# Charging.net
KiCad netlist of a schematic drawn in Altium Designer
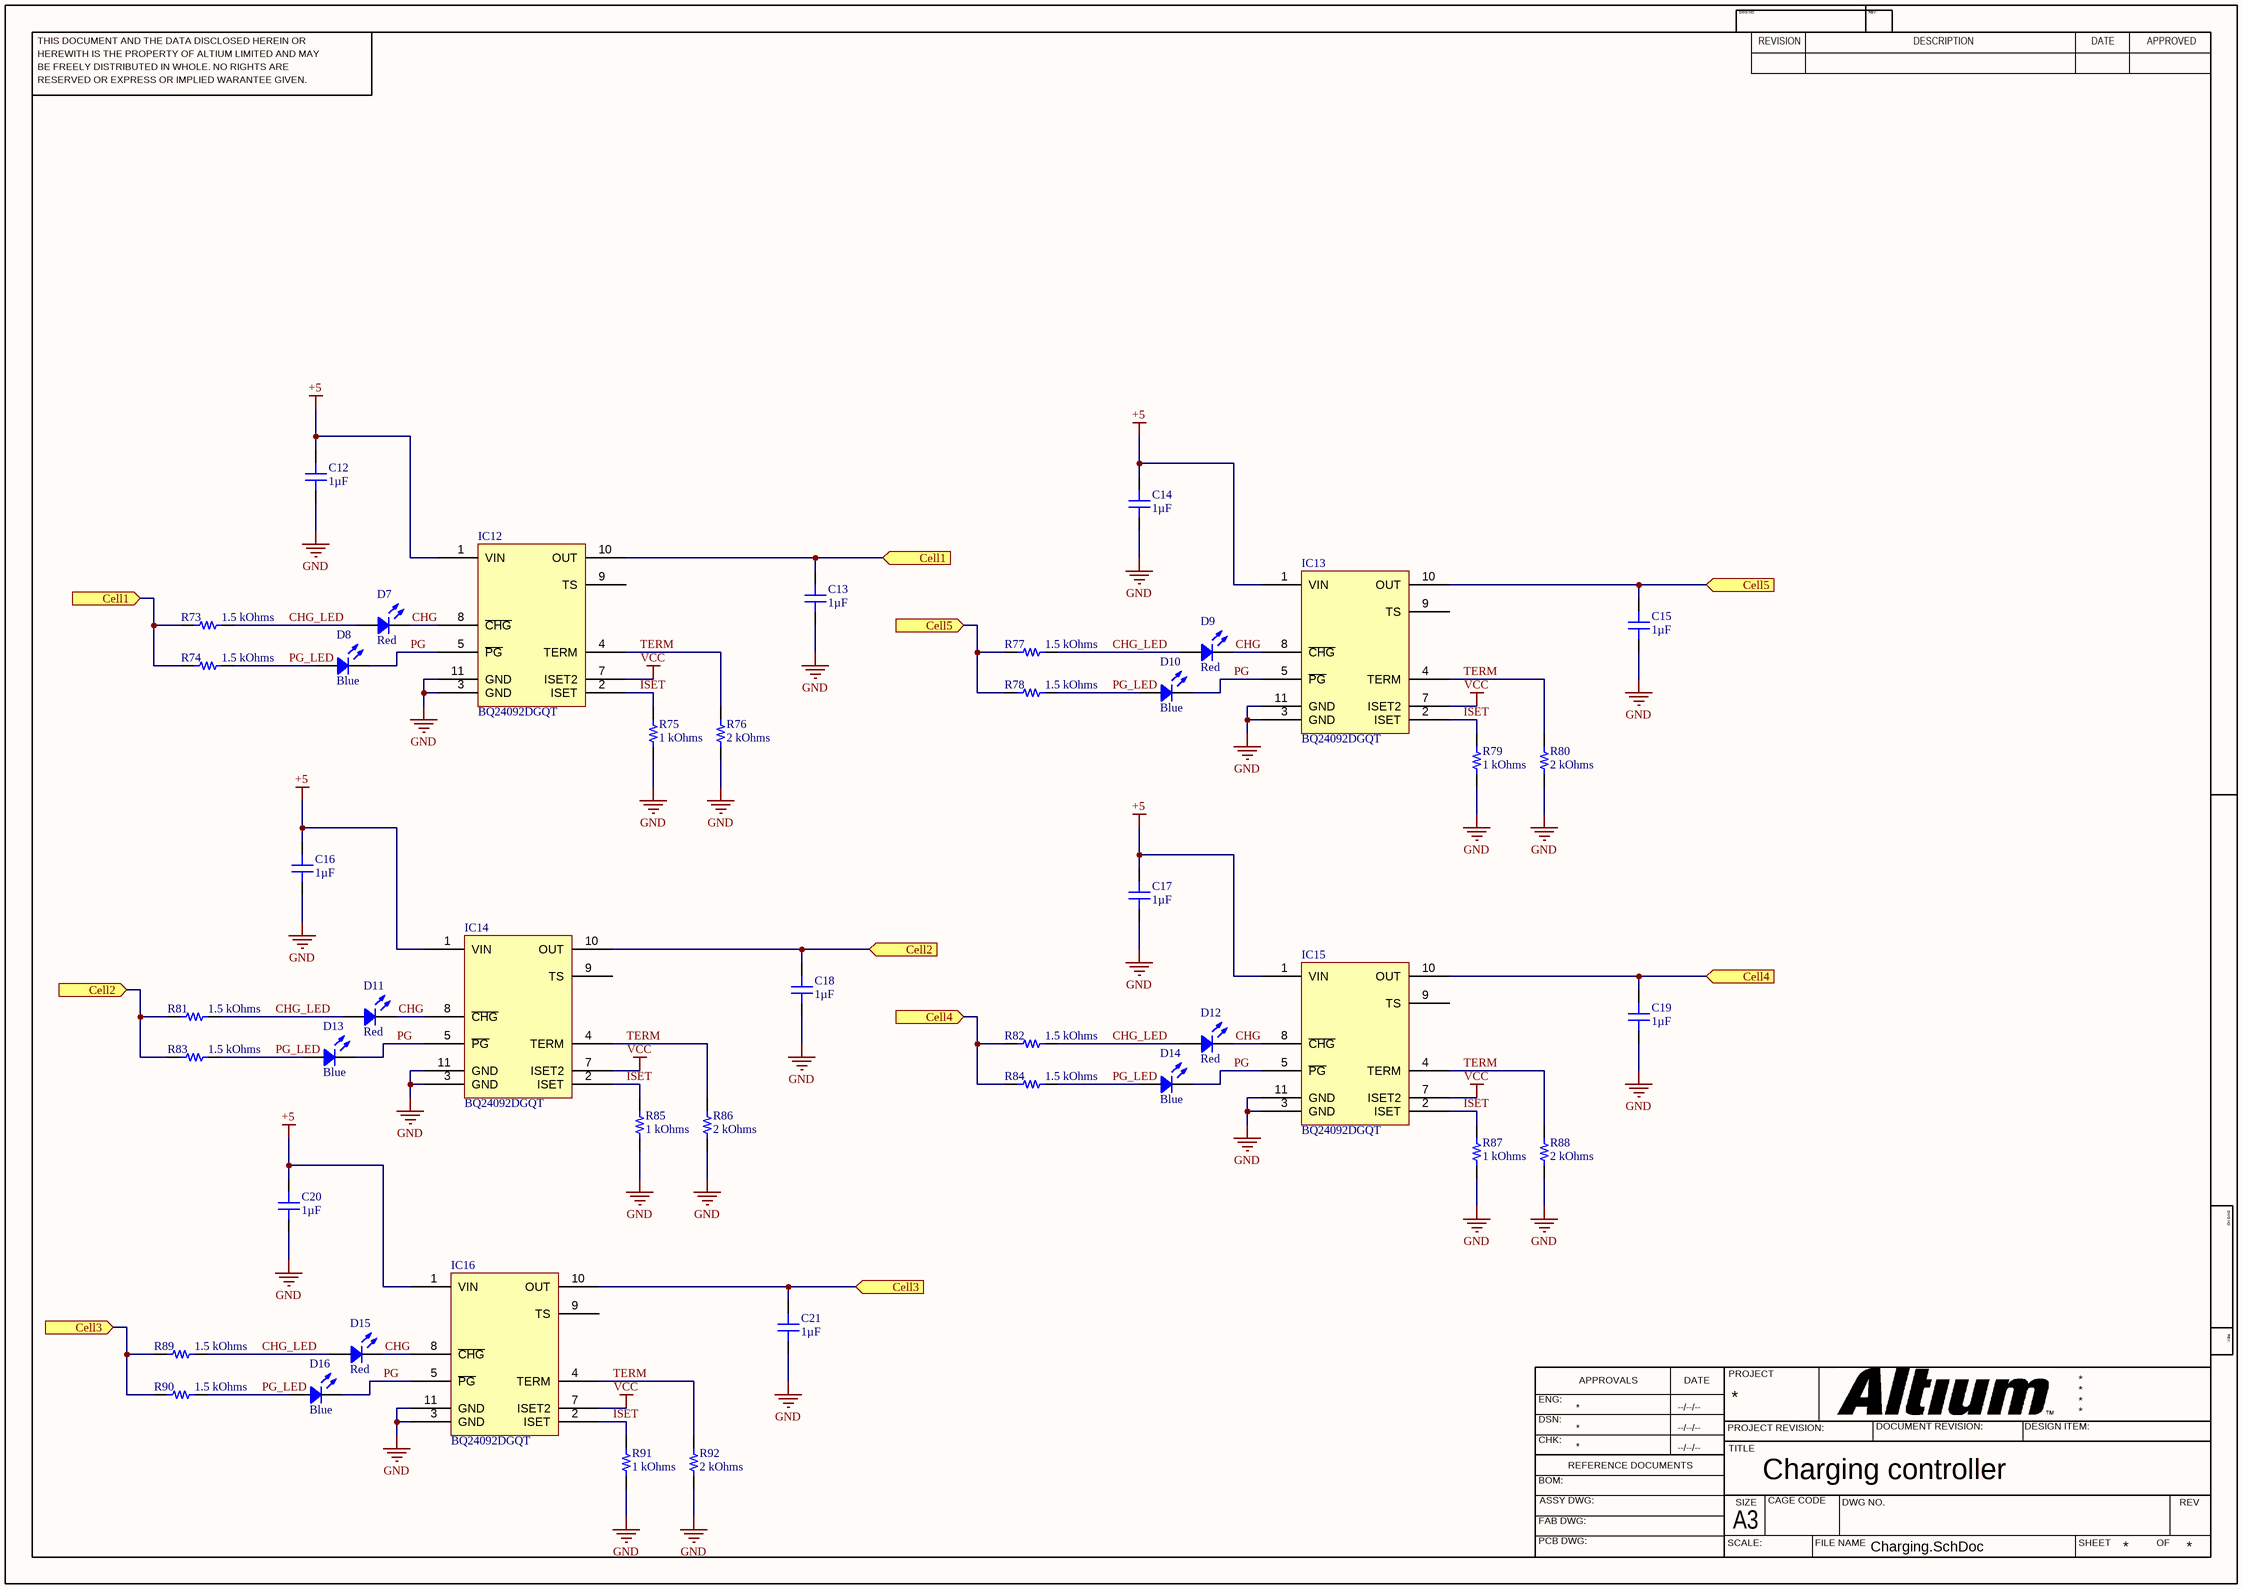
[diagram p0: Charging.SchDoc]

(export (version "E")
  (design (tool "Eeschema 10.0.6"))
  (components
    (comp (ref "C12")
      (value "1µF")
      (footprint "CAP 0603_1608")
      (description "CAP CER 1UF 25V X5R 0603")
      (fields (field (name "PART NUMBER") "CC0603KRX5R8BB105") (field (name "MANUFACTURER") "Yageo"))
      (libsource (lib "Celestial Altium Library - altium_library") (part "Capacitor"))
    )
    (comp (ref "C13")
      (value "1µF")
      (footprint "CAP 0603_1608")
      (description "CAP CER 1UF 25V X5R 0603")
      (fields (field (name "PART NUMBER") "CC0603KRX5R8BB105") (field (name "MANUFACTURER") "Yageo"))
      (libsource (lib "Celestial Altium Library - altium_library") (part "Capacitor"))
    )
    (comp (ref "C14")
      (value "1µF")
      (footprint "CAP 0603_1608")
      (description "CAP CER 1UF 25V X5R 0603")
      (fields (field (name "PART NUMBER") "CC0603KRX5R8BB105") (field (name "MANUFACTURER") "Yageo"))
      (libsource (lib "Celestial Altium Library - altium_library") (part "Capacitor"))
    )
    (comp (ref "C15")
      (value "1µF")
      (footprint "CAP 0603_1608")
      (description "CAP CER 1UF 25V X5R 0603")
      (fields (field (name "PART NUMBER") "CC0603KRX5R8BB105") (field (name "MANUFACTURER") "Yageo"))
      (libsource (lib "Celestial Altium Library - altium_library") (part "Capacitor"))
    )
    (comp (ref "C16")
      (value "1µF")
      (footprint "CAP 0603_1608")
      (description "CAP CER 1UF 25V X5R 0603")
      (fields (field (name "PART NUMBER") "CC0603KRX5R8BB105") (field (name "MANUFACTURER") "Yageo"))
      (libsource (lib "Celestial Altium Library - altium_library") (part "Capacitor"))
    )
    (comp (ref "C17")
      (value "1µF")
      (footprint "CAP 0603_1608")
      (description "CAP CER 1UF 25V X5R 0603")
      (fields (field (name "PART NUMBER") "CC0603KRX5R8BB105") (field (name "MANUFACTURER") "Yageo"))
      (libsource (lib "Celestial Altium Library - altium_library") (part "Capacitor"))
    )
    (comp (ref "C18")
      (value "1µF")
      (footprint "CAP 0603_1608")
      (description "CAP CER 1UF 25V X5R 0603")
      (fields (field (name "PART NUMBER") "CC0603KRX5R8BB105") (field (name "MANUFACTURER") "Yageo"))
      (libsource (lib "Celestial Altium Library - altium_library") (part "Capacitor"))
    )
    (comp (ref "C19")
      (value "1µF")
      (footprint "CAP 0603_1608")
      (description "CAP CER 1UF 25V X5R 0603")
      (fields (field (name "PART NUMBER") "CC0603KRX5R8BB105") (field (name "MANUFACTURER") "Yageo"))
      (libsource (lib "Celestial Altium Library - altium_library") (part "Capacitor"))
    )
    (comp (ref "C20")
      (value "1µF")
      (footprint "CAP 0603_1608")
      (description "CAP CER 1UF 25V X5R 0603")
      (fields (field (name "PART NUMBER") "CC0603KRX5R8BB105") (field (name "MANUFACTURER") "Yageo"))
      (libsource (lib "Celestial Altium Library - altium_library") (part "Capacitor"))
    )
    (comp (ref "C21")
      (value "1µF")
      (footprint "CAP 0603_1608")
      (description "CAP CER 1UF 25V X5R 0603")
      (fields (field (name "PART NUMBER") "CC0603KRX5R8BB105") (field (name "MANUFACTURER") "Yageo"))
      (libsource (lib "Celestial Altium Library - altium_library") (part "Capacitor"))
    )
    (comp (ref "D7")
      (value "Red")
      (footprint "LED 0603_1608 RED")
      (description "LED RED CLEAR 2SMD")
      (fields
        (field (name "PART NUMBER") "19-213USRC/S259/TR8")
        (field (name "MANUFACTURER") "Everlight Electronics Co Ltd")
      )
      (libsource (lib "Celestial Altium Library - altium_library") (part "LED"))
    )
    (comp (ref "D8")
      (value "Blue")
      (footprint "LED 0603_1608 BLUE")
      (description "LED BLUE CLEAR 2SMD")
      (fields
        (field (name "PART NUMBER") "EAST16084BA8")
        (field (name "MANUFACTURER") "Everlight Electronics Co Ltd")
      )
      (libsource (lib "Celestial Altium Library - altium_library") (part "LED"))
    )
    (comp (ref "D9")
      (value "Red")
      (footprint "LED 0603_1608 RED")
      (description "LED RED CLEAR 2SMD")
      (fields
        (field (name "PART NUMBER") "19-213USRC/S259/TR8")
        (field (name "MANUFACTURER") "Everlight Electronics Co Ltd")
      )
      (libsource (lib "Celestial Altium Library - altium_library") (part "LED"))
    )
    (comp (ref "D10")
      (value "Blue")
      (footprint "LED 0603_1608 BLUE")
      (description "LED BLUE CLEAR 2SMD")
      (fields
        (field (name "PART NUMBER") "EAST16084BA8")
        (field (name "MANUFACTURER") "Everlight Electronics Co Ltd")
      )
      (libsource (lib "Celestial Altium Library - altium_library") (part "LED"))
    )
    (comp (ref "D11")
      (value "Red")
      (footprint "LED 0603_1608 RED")
      (description "LED RED CLEAR 2SMD")
      (fields
        (field (name "PART NUMBER") "19-213USRC/S259/TR8")
        (field (name "MANUFACTURER") "Everlight Electronics Co Ltd")
      )
      (libsource (lib "Celestial Altium Library - altium_library") (part "LED"))
    )
    (comp (ref "D12")
      (value "Red")
      (footprint "LED 0603_1608 RED")
      (description "LED RED CLEAR 2SMD")
      (fields
        (field (name "PART NUMBER") "19-213USRC/S259/TR8")
        (field (name "MANUFACTURER") "Everlight Electronics Co Ltd")
      )
      (libsource (lib "Celestial Altium Library - altium_library") (part "LED"))
    )
    (comp (ref "D13")
      (value "Blue")
      (footprint "LED 0603_1608 BLUE")
      (description "LED BLUE CLEAR 2SMD")
      (fields
        (field (name "PART NUMBER") "EAST16084BA8")
        (field (name "MANUFACTURER") "Everlight Electronics Co Ltd")
      )
      (libsource (lib "Celestial Altium Library - altium_library") (part "LED"))
    )
    (comp (ref "D14")
      (value "Blue")
      (footprint "LED 0603_1608 BLUE")
      (description "LED BLUE CLEAR 2SMD")
      (fields
        (field (name "PART NUMBER") "EAST16084BA8")
        (field (name "MANUFACTURER") "Everlight Electronics Co Ltd")
      )
      (libsource (lib "Celestial Altium Library - altium_library") (part "LED"))
    )
    (comp (ref "D15")
      (value "Red")
      (footprint "LED 0603_1608 RED")
      (description "LED RED CLEAR 2SMD")
      (fields
        (field (name "PART NUMBER") "19-213USRC/S259/TR8")
        (field (name "MANUFACTURER") "Everlight Electronics Co Ltd")
      )
      (libsource (lib "Celestial Altium Library - altium_library") (part "LED"))
    )
    (comp (ref "D16")
      (value "Blue")
      (footprint "LED 0603_1608 BLUE")
      (description "LED BLUE CLEAR 2SMD")
      (fields
        (field (name "PART NUMBER") "EAST16084BA8")
        (field (name "MANUFACTURER") "Everlight Electronics Co Ltd")
      )
      (libsource (lib "Celestial Altium Library - altium_library") (part "LED"))
    )
    (comp (ref "IC12")
      (value "BQ24092DGQT")
      (footprint "TI PDSO-10 DCQ")
      (description "IC BATT CHARGER LI-ION 10MSOP")
      (fields (field (name "MANUFACTURER") "Texas Instruments"))
      (libsource (lib "Celestial Altium Library - altium_library") (part "TI BQ2409x"))
    )
    (comp (ref "IC13")
      (value "BQ24092DGQT")
      (footprint "TI PDSO-10 DCQ")
      (description "IC BATT CHARGER LI-ION 10MSOP")
      (fields (field (name "MANUFACTURER") "Texas Instruments"))
      (libsource (lib "Celestial Altium Library - altium_library") (part "TI BQ2409x"))
    )
    (comp (ref "IC14")
      (value "BQ24092DGQT")
      (footprint "TI PDSO-10 DCQ")
      (description "IC BATT CHARGER LI-ION 10MSOP")
      (fields (field (name "MANUFACTURER") "Texas Instruments"))
      (libsource (lib "Celestial Altium Library - altium_library") (part "TI BQ2409x"))
    )
    (comp (ref "IC15")
      (value "BQ24092DGQT")
      (footprint "TI PDSO-10 DCQ")
      (description "IC BATT CHARGER LI-ION 10MSOP")
      (fields (field (name "MANUFACTURER") "Texas Instruments"))
      (libsource (lib "Celestial Altium Library - altium_library") (part "TI BQ2409x"))
    )
    (comp (ref "IC16")
      (value "BQ24092DGQT")
      (footprint "TI PDSO-10 DCQ")
      (description "IC BATT CHARGER LI-ION 10MSOP")
      (fields (field (name "MANUFACTURER") "Texas Instruments"))
      (libsource (lib "Celestial Altium Library - altium_library") (part "TI BQ2409x"))
    )
    (comp (ref "R73")
      (value "1.5 kOhms")
      (footprint "RES 0603_1608")
      (description "RES SMD 1.5K OHM 1% 1/10W 0603")
      (fields
        (field (name "PART NUMBER") "ERJ-3EKF1501V")
        (field (name "MANUFACTURER") "Panasonic Electronic Components")
      )
      (libsource (lib "Celestial Altium Library - altium_library") (part "Resistor"))
    )
    (comp (ref "R74")
      (value "1.5 kOhms")
      (footprint "RES 0603_1608")
      (description "RES SMD 1.5K OHM 1% 1/10W 0603")
      (fields
        (field (name "PART NUMBER") "ERJ-3EKF1501V")
        (field (name "MANUFACTURER") "Panasonic Electronic Components")
      )
      (libsource (lib "Celestial Altium Library - altium_library") (part "Resistor"))
    )
    (comp (ref "R75")
      (value "1 kOhms")
      (footprint "RES 0603_1608")
      (description "RES SMD 1K OHM 5% 1/4W 0603")
      (fields
        (field (name "PART NUMBER") "ERJ-PA3J102V")
        (field (name "MANUFACTURER") "Panasonic Electronic Components")
      )
      (libsource (lib "Celestial Altium Library - altium_library") (part "Resistor"))
    )
    (comp (ref "R76")
      (value "2 kOhms")
      (footprint "RES 0603_1608")
      (description "RES SMD 2K OHM 5% 1/4W 0603")
      (fields
        (field (name "PART NUMBER") "ERJ-PA3J202V")
        (field (name "MANUFACTURER") "Panasonic Electronic Components")
      )
      (libsource (lib "Celestial Altium Library - altium_library") (part "Resistor"))
    )
    (comp (ref "R77")
      (value "1.5 kOhms")
      (footprint "RES 0603_1608")
      (description "RES SMD 1.5K OHM 1% 1/10W 0603")
      (fields
        (field (name "PART NUMBER") "ERJ-3EKF1501V")
        (field (name "MANUFACTURER") "Panasonic Electronic Components")
      )
      (libsource (lib "Celestial Altium Library - altium_library") (part "Resistor"))
    )
    (comp (ref "R78")
      (value "1.5 kOhms")
      (footprint "RES 0603_1608")
      (description "RES SMD 1.5K OHM 1% 1/10W 0603")
      (fields
        (field (name "PART NUMBER") "ERJ-3EKF1501V")
        (field (name "MANUFACTURER") "Panasonic Electronic Components")
      )
      (libsource (lib "Celestial Altium Library - altium_library") (part "Resistor"))
    )
    (comp (ref "R79")
      (value "1 kOhms")
      (footprint "RES 0603_1608")
      (description "RES SMD 1K OHM 5% 1/4W 0603")
      (fields
        (field (name "PART NUMBER") "ERJ-PA3J102V")
        (field (name "MANUFACTURER") "Panasonic Electronic Components")
      )
      (libsource (lib "Celestial Altium Library - altium_library") (part "Resistor"))
    )
    (comp (ref "R80")
      (value "2 kOhms")
      (footprint "RES 0603_1608")
      (description "RES SMD 2K OHM 5% 1/4W 0603")
      (fields
        (field (name "PART NUMBER") "ERJ-PA3J202V")
        (field (name "MANUFACTURER") "Panasonic Electronic Components")
      )
      (libsource (lib "Celestial Altium Library - altium_library") (part "Resistor"))
    )
    (comp (ref "R81")
      (value "1.5 kOhms")
      (footprint "RES 0603_1608")
      (description "RES SMD 1.5K OHM 1% 1/10W 0603")
      (fields
        (field (name "PART NUMBER") "ERJ-3EKF1501V")
        (field (name "MANUFACTURER") "Panasonic Electronic Components")
      )
      (libsource (lib "Celestial Altium Library - altium_library") (part "Resistor"))
    )
    (comp (ref "R82")
      (value "1.5 kOhms")
      (footprint "RES 0603_1608")
      (description "RES SMD 1.5K OHM 1% 1/10W 0603")
      (fields
        (field (name "PART NUMBER") "ERJ-3EKF1501V")
        (field (name "MANUFACTURER") "Panasonic Electronic Components")
      )
      (libsource (lib "Celestial Altium Library - altium_library") (part "Resistor"))
    )
    (comp (ref "R83")
      (value "1.5 kOhms")
      (footprint "RES 0603_1608")
      (description "RES SMD 1.5K OHM 1% 1/10W 0603")
      (fields
        (field (name "PART NUMBER") "ERJ-3EKF1501V")
        (field (name "MANUFACTURER") "Panasonic Electronic Components")
      )
      (libsource (lib "Celestial Altium Library - altium_library") (part "Resistor"))
    )
    (comp (ref "R84")
      (value "1.5 kOhms")
      (footprint "RES 0603_1608")
      (description "RES SMD 1.5K OHM 1% 1/10W 0603")
      (fields
        (field (name "PART NUMBER") "ERJ-3EKF1501V")
        (field (name "MANUFACTURER") "Panasonic Electronic Components")
      )
      (libsource (lib "Celestial Altium Library - altium_library") (part "Resistor"))
    )
    (comp (ref "R85")
      (value "1 kOhms")
      (footprint "RES 0603_1608")
      (description "RES SMD 1K OHM 5% 1/4W 0603")
      (fields
        (field (name "PART NUMBER") "ERJ-PA3J102V")
        (field (name "MANUFACTURER") "Panasonic Electronic Components")
      )
      (libsource (lib "Celestial Altium Library - altium_library") (part "Resistor"))
    )
    (comp (ref "R86")
      (value "2 kOhms")
      (footprint "RES 0603_1608")
      (description "RES SMD 2K OHM 5% 1/4W 0603")
      (fields
        (field (name "PART NUMBER") "ERJ-PA3J202V")
        (field (name "MANUFACTURER") "Panasonic Electronic Components")
      )
      (libsource (lib "Celestial Altium Library - altium_library") (part "Resistor"))
    )
    (comp (ref "R87")
      (value "1 kOhms")
      (footprint "RES 0603_1608")
      (description "RES SMD 1K OHM 5% 1/4W 0603")
      (fields
        (field (name "PART NUMBER") "ERJ-PA3J102V")
        (field (name "MANUFACTURER") "Panasonic Electronic Components")
      )
      (libsource (lib "Celestial Altium Library - altium_library") (part "Resistor"))
    )
    (comp (ref "R88")
      (value "2 kOhms")
      (footprint "RES 0603_1608")
      (description "RES SMD 2K OHM 5% 1/4W 0603")
      (fields
        (field (name "PART NUMBER") "ERJ-PA3J202V")
        (field (name "MANUFACTURER") "Panasonic Electronic Components")
      )
      (libsource (lib "Celestial Altium Library - altium_library") (part "Resistor"))
    )
    (comp (ref "R89")
      (value "1.5 kOhms")
      (footprint "RES 0603_1608")
      (description "RES SMD 1.5K OHM 1% 1/10W 0603")
      (fields
        (field (name "PART NUMBER") "ERJ-3EKF1501V")
        (field (name "MANUFACTURER") "Panasonic Electronic Components")
      )
      (libsource (lib "Celestial Altium Library - altium_library") (part "Resistor"))
    )
    (comp (ref "R90")
      (value "1.5 kOhms")
      (footprint "RES 0603_1608")
      (description "RES SMD 1.5K OHM 1% 1/10W 0603")
      (fields
        (field (name "PART NUMBER") "ERJ-3EKF1501V")
        (field (name "MANUFACTURER") "Panasonic Electronic Components")
      )
      (libsource (lib "Celestial Altium Library - altium_library") (part "Resistor"))
    )
    (comp (ref "R91")
      (value "1 kOhms")
      (footprint "RES 0603_1608")
      (description "RES SMD 1K OHM 5% 1/4W 0603")
      (fields
        (field (name "PART NUMBER") "ERJ-PA3J102V")
        (field (name "MANUFACTURER") "Panasonic Electronic Components")
      )
      (libsource (lib "Celestial Altium Library - altium_library") (part "Resistor"))
    )
    (comp (ref "R92")
      (value "2 kOhms")
      (footprint "RES 0603_1608")
      (description "RES SMD 2K OHM 5% 1/4W 0603")
      (fields
        (field (name "PART NUMBER") "ERJ-PA3J202V")
        (field (name "MANUFACTURER") "Panasonic Electronic Components")
      )
      (libsource (lib "Celestial Altium Library - altium_library") (part "Resistor"))
    )
  )
  (nets
    (net (code "1") (name "+5") (class "Default")
      (node (ref "C12") (pin "2") (pinfunction "2_2") (pintype "passive"))
      (node (ref "C14") (pin "2") (pinfunction "2_2") (pintype "passive"))
      (node (ref "C16") (pin "2") (pinfunction "2_2") (pintype "passive"))
      (node (ref "C17") (pin "2") (pinfunction "2_2") (pintype "passive"))
      (node (ref "C20") (pin "2") (pinfunction "2_2") (pintype "passive"))
      (node (ref "IC12") (pin "1") (pinfunction "VIN_1") (pintype "passive"))
      (node (ref "IC13") (pin "1") (pinfunction "VIN_1") (pintype "passive"))
      (node (ref "IC14") (pin "1") (pinfunction "VIN_1") (pintype "passive"))
      (node (ref "IC15") (pin "1") (pinfunction "VIN_1") (pintype "passive"))
      (node (ref "IC16") (pin "1") (pinfunction "VIN_1") (pintype "passive"))
    )
    (net (code "2") (name "/CHG") (class "Default")
      (node (ref "D11") (pin "2") (pinfunction "2_2") (pintype "passive"))
      (node (ref "D12") (pin "2") (pinfunction "2_2") (pintype "passive"))
      (node (ref "D15") (pin "2") (pinfunction "2_2") (pintype "passive"))
      (node (ref "D7") (pin "2") (pinfunction "2_2") (pintype "passive"))
      (node (ref "D9") (pin "2") (pinfunction "2_2") (pintype "passive"))
      (node (ref "IC12") (pin "8") (pinfunction "~{CHG}_8") (pintype "passive"))
      (node (ref "IC13") (pin "8") (pinfunction "~{CHG}_8") (pintype "passive"))
      (node (ref "IC14") (pin "8") (pinfunction "~{CHG}_8") (pintype "passive"))
      (node (ref "IC15") (pin "8") (pinfunction "~{CHG}_8") (pintype "passive"))
      (node (ref "IC16") (pin "8") (pinfunction "~{CHG}_8") (pintype "passive"))
    )
    (net (code "3") (name "/CHG_LED") (class "Default")
      (node (ref "D11") (pin "1") (pinfunction "1_1") (pintype "passive"))
      (node (ref "D12") (pin "1") (pinfunction "1_1") (pintype "passive"))
      (node (ref "D15") (pin "1") (pinfunction "1_1") (pintype "passive"))
      (node (ref "D7") (pin "1") (pinfunction "1_1") (pintype "passive"))
      (node (ref "D9") (pin "1") (pinfunction "1_1") (pintype "passive"))
      (node (ref "R73") (pin "2") (pinfunction "2_2") (pintype "passive"))
      (node (ref "R77") (pin "2") (pinfunction "2_2") (pintype "passive"))
      (node (ref "R81") (pin "2") (pinfunction "2_2") (pintype "passive"))
      (node (ref "R82") (pin "2") (pinfunction "2_2") (pintype "passive"))
      (node (ref "R89") (pin "2") (pinfunction "2_2") (pintype "passive"))
    )
    (net (code "4") (name "/Cell1") (class "Default")
      (node (ref "C13") (pin "2") (pinfunction "2_2") (pintype "passive"))
      (node (ref "IC12") (pin "10") (pinfunction "OUT_10") (pintype "passive"))
      (node (ref "R73") (pin "1") (pinfunction "1_1") (pintype "passive"))
      (node (ref "R74") (pin "1") (pinfunction "1_1") (pintype "passive"))
    )
    (net (code "5") (name "/Cell2") (class "Default")
      (node (ref "C18") (pin "2") (pinfunction "2_2") (pintype "passive"))
      (node (ref "IC14") (pin "10") (pinfunction "OUT_10") (pintype "passive"))
      (node (ref "R81") (pin "1") (pinfunction "1_1") (pintype "passive"))
      (node (ref "R83") (pin "1") (pinfunction "1_1") (pintype "passive"))
    )
    (net (code "6") (name "/Cell3") (class "Default")
      (node (ref "C21") (pin "2") (pinfunction "2_2") (pintype "passive"))
      (node (ref "IC16") (pin "10") (pinfunction "OUT_10") (pintype "passive"))
      (node (ref "R89") (pin "1") (pinfunction "1_1") (pintype "passive"))
      (node (ref "R90") (pin "1") (pinfunction "1_1") (pintype "passive"))
    )
    (net (code "7") (name "/Cell4") (class "Default")
      (node (ref "C19") (pin "2") (pinfunction "2_2") (pintype "passive"))
      (node (ref "IC15") (pin "10") (pinfunction "OUT_10") (pintype "passive"))
      (node (ref "R82") (pin "1") (pinfunction "1_1") (pintype "passive"))
      (node (ref "R84") (pin "1") (pinfunction "1_1") (pintype "passive"))
    )
    (net (code "8") (name "/Cell5") (class "Default")
      (node (ref "C15") (pin "2") (pinfunction "2_2") (pintype "passive"))
      (node (ref "IC13") (pin "10") (pinfunction "OUT_10") (pintype "passive"))
      (node (ref "R77") (pin "1") (pinfunction "1_1") (pintype "passive"))
      (node (ref "R78") (pin "1") (pinfunction "1_1") (pintype "passive"))
    )
    (net (code "9") (name "/ISET") (class "Default")
      (node (ref "IC12") (pin "2") (pinfunction "ISET_2") (pintype "passive"))
      (node (ref "IC13") (pin "2") (pinfunction "ISET_2") (pintype "passive"))
      (node (ref "IC14") (pin "2") (pinfunction "ISET_2") (pintype "passive"))
      (node (ref "IC15") (pin "2") (pinfunction "ISET_2") (pintype "passive"))
      (node (ref "IC16") (pin "2") (pinfunction "ISET_2") (pintype "passive"))
      (node (ref "R75") (pin "2") (pinfunction "2_2") (pintype "passive"))
      (node (ref "R79") (pin "2") (pinfunction "2_2") (pintype "passive"))
      (node (ref "R85") (pin "2") (pinfunction "2_2") (pintype "passive"))
      (node (ref "R87") (pin "2") (pinfunction "2_2") (pintype "passive"))
      (node (ref "R91") (pin "2") (pinfunction "2_2") (pintype "passive"))
    )
    (net (code "10") (name "/PG") (class "Default")
      (node (ref "D10") (pin "2") (pinfunction "2_2") (pintype "passive"))
      (node (ref "D13") (pin "2") (pinfunction "2_2") (pintype "passive"))
      (node (ref "D14") (pin "2") (pinfunction "2_2") (pintype "passive"))
      (node (ref "D16") (pin "2") (pinfunction "2_2") (pintype "passive"))
      (node (ref "D8") (pin "2") (pinfunction "2_2") (pintype "passive"))
      (node (ref "IC12") (pin "5") (pinfunction "~{PG}_5") (pintype "passive"))
      (node (ref "IC13") (pin "5") (pinfunction "~{PG}_5") (pintype "passive"))
      (node (ref "IC14") (pin "5") (pinfunction "~{PG}_5") (pintype "passive"))
      (node (ref "IC15") (pin "5") (pinfunction "~{PG}_5") (pintype "passive"))
      (node (ref "IC16") (pin "5") (pinfunction "~{PG}_5") (pintype "passive"))
    )
    (net (code "11") (name "/PG_LED") (class "Default")
      (node (ref "D10") (pin "1") (pinfunction "1_1") (pintype "passive"))
      (node (ref "D13") (pin "1") (pinfunction "1_1") (pintype "passive"))
      (node (ref "D14") (pin "1") (pinfunction "1_1") (pintype "passive"))
      (node (ref "D16") (pin "1") (pinfunction "1_1") (pintype "passive"))
      (node (ref "D8") (pin "1") (pinfunction "1_1") (pintype "passive"))
      (node (ref "R74") (pin "2") (pinfunction "2_2") (pintype "passive"))
      (node (ref "R78") (pin "2") (pinfunction "2_2") (pintype "passive"))
      (node (ref "R83") (pin "2") (pinfunction "2_2") (pintype "passive"))
      (node (ref "R84") (pin "2") (pinfunction "2_2") (pintype "passive"))
      (node (ref "R90") (pin "2") (pinfunction "2_2") (pintype "passive"))
    )
    (net (code "12") (name "/TERM") (class "Default")
      (node (ref "IC12") (pin "4") (pinfunction "TERM_4") (pintype "passive"))
      (node (ref "IC13") (pin "4") (pinfunction "TERM_4") (pintype "passive"))
      (node (ref "IC14") (pin "4") (pinfunction "TERM_4") (pintype "passive"))
      (node (ref "IC15") (pin "4") (pinfunction "TERM_4") (pintype "passive"))
      (node (ref "IC16") (pin "4") (pinfunction "TERM_4") (pintype "passive"))
      (node (ref "R76") (pin "2") (pinfunction "2_2") (pintype "passive"))
      (node (ref "R80") (pin "2") (pinfunction "2_2") (pintype "passive"))
      (node (ref "R86") (pin "2") (pinfunction "2_2") (pintype "passive"))
      (node (ref "R88") (pin "2") (pinfunction "2_2") (pintype "passive"))
      (node (ref "R92") (pin "2") (pinfunction "2_2") (pintype "passive"))
    )
    (net (code "13") (name "GND") (class "Default")
      (node (ref "C12") (pin "1") (pinfunction "1_1") (pintype "passive"))
      (node (ref "C13") (pin "1") (pinfunction "1_1") (pintype "passive"))
      (node (ref "C14") (pin "1") (pinfunction "1_1") (pintype "passive"))
      (node (ref "C15") (pin "1") (pinfunction "1_1") (pintype "passive"))
      (node (ref "C16") (pin "1") (pinfunction "1_1") (pintype "passive"))
      (node (ref "C17") (pin "1") (pinfunction "1_1") (pintype "passive"))
      (node (ref "C18") (pin "1") (pinfunction "1_1") (pintype "passive"))
      (node (ref "C19") (pin "1") (pinfunction "1_1") (pintype "passive"))
      (node (ref "C20") (pin "1") (pinfunction "1_1") (pintype "passive"))
      (node (ref "C21") (pin "1") (pinfunction "1_1") (pintype "passive"))
      (node (ref "IC12") (pin "11") (pinfunction "GND_11") (pintype "passive"))
      (node (ref "IC12") (pin "3") (pinfunction "GND_3") (pintype "passive"))
      (node (ref "IC13") (pin "11") (pinfunction "GND_11") (pintype "passive"))
      (node (ref "IC13") (pin "3") (pinfunction "GND_3") (pintype "passive"))
      (node (ref "IC14") (pin "11") (pinfunction "GND_11") (pintype "passive"))
      (node (ref "IC14") (pin "3") (pinfunction "GND_3") (pintype "passive"))
      (node (ref "IC15") (pin "11") (pinfunction "GND_11") (pintype "passive"))
      (node (ref "IC15") (pin "3") (pinfunction "GND_3") (pintype "passive"))
      (node (ref "IC16") (pin "11") (pinfunction "GND_11") (pintype "passive"))
      (node (ref "IC16") (pin "3") (pinfunction "GND_3") (pintype "passive"))
      (node (ref "R75") (pin "1") (pinfunction "1_1") (pintype "passive"))
      (node (ref "R76") (pin "1") (pinfunction "1_1") (pintype "passive"))
      (node (ref "R79") (pin "1") (pinfunction "1_1") (pintype "passive"))
      (node (ref "R80") (pin "1") (pinfunction "1_1") (pintype "passive"))
      (node (ref "R85") (pin "1") (pinfunction "1_1") (pintype "passive"))
      (node (ref "R86") (pin "1") (pinfunction "1_1") (pintype "passive"))
      (node (ref "R87") (pin "1") (pinfunction "1_1") (pintype "passive"))
      (node (ref "R88") (pin "1") (pinfunction "1_1") (pintype "passive"))
      (node (ref "R91") (pin "1") (pinfunction "1_1") (pintype "passive"))
      (node (ref "R92") (pin "1") (pinfunction "1_1") (pintype "passive"))
    )
    (net (code "14") (name "VCC") (class "Default")
      (node (ref "IC12") (pin "7") (pinfunction "ISET2_7") (pintype "passive"))
      (node (ref "IC13") (pin "7") (pinfunction "ISET2_7") (pintype "passive"))
      (node (ref "IC14") (pin "7") (pinfunction "ISET2_7") (pintype "passive"))
      (node (ref "IC15") (pin "7") (pinfunction "ISET2_7") (pintype "passive"))
      (node (ref "IC16") (pin "7") (pinfunction "ISET2_7") (pintype "passive"))
    )
    (net (code "15") (name "unconnected-(IC12-TS-Pad9)") (class "Default")
      (node (ref "IC12") (pin "9") (pinfunction "TS_9") (pintype "passive"))
    )
    (net (code "16") (name "unconnected-(IC13-TS-Pad9)") (class "Default")
      (node (ref "IC13") (pin "9") (pinfunction "TS_9") (pintype "passive"))
    )
    (net (code "17") (name "unconnected-(IC14-TS-Pad9)") (class "Default")
      (node (ref "IC14") (pin "9") (pinfunction "TS_9") (pintype "passive"))
    )
    (net (code "18") (name "unconnected-(IC15-TS-Pad9)") (class "Default")
      (node (ref "IC15") (pin "9") (pinfunction "TS_9") (pintype "passive"))
    )
    (net (code "19") (name "unconnected-(IC16-TS-Pad9)") (class "Default")
      (node (ref "IC16") (pin "9") (pinfunction "TS_9") (pintype "passive"))
    )
  )
)
